# B45100557C.net
KiCad netlist of a schematic drawn in Altium Designer
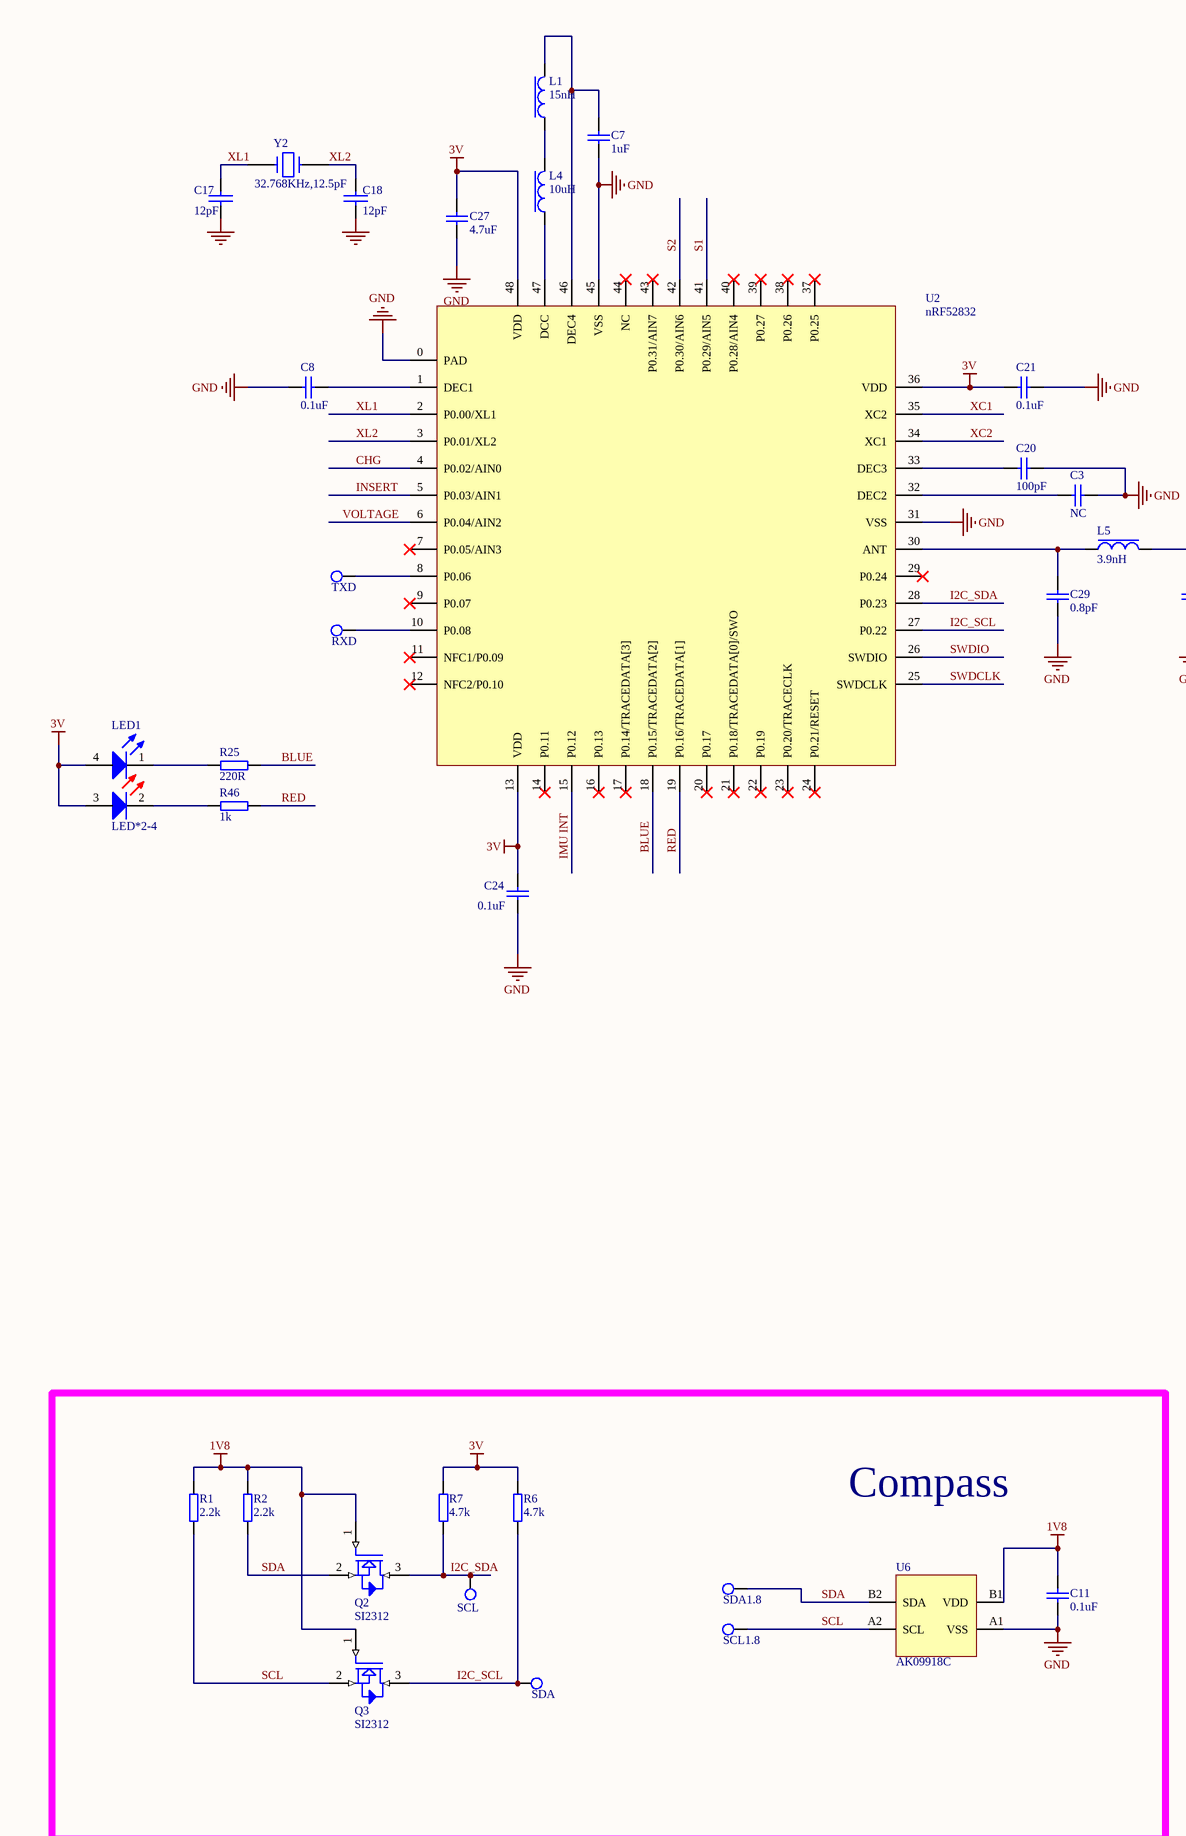
[diagram p0: B45100557C.SCHDOC, left]
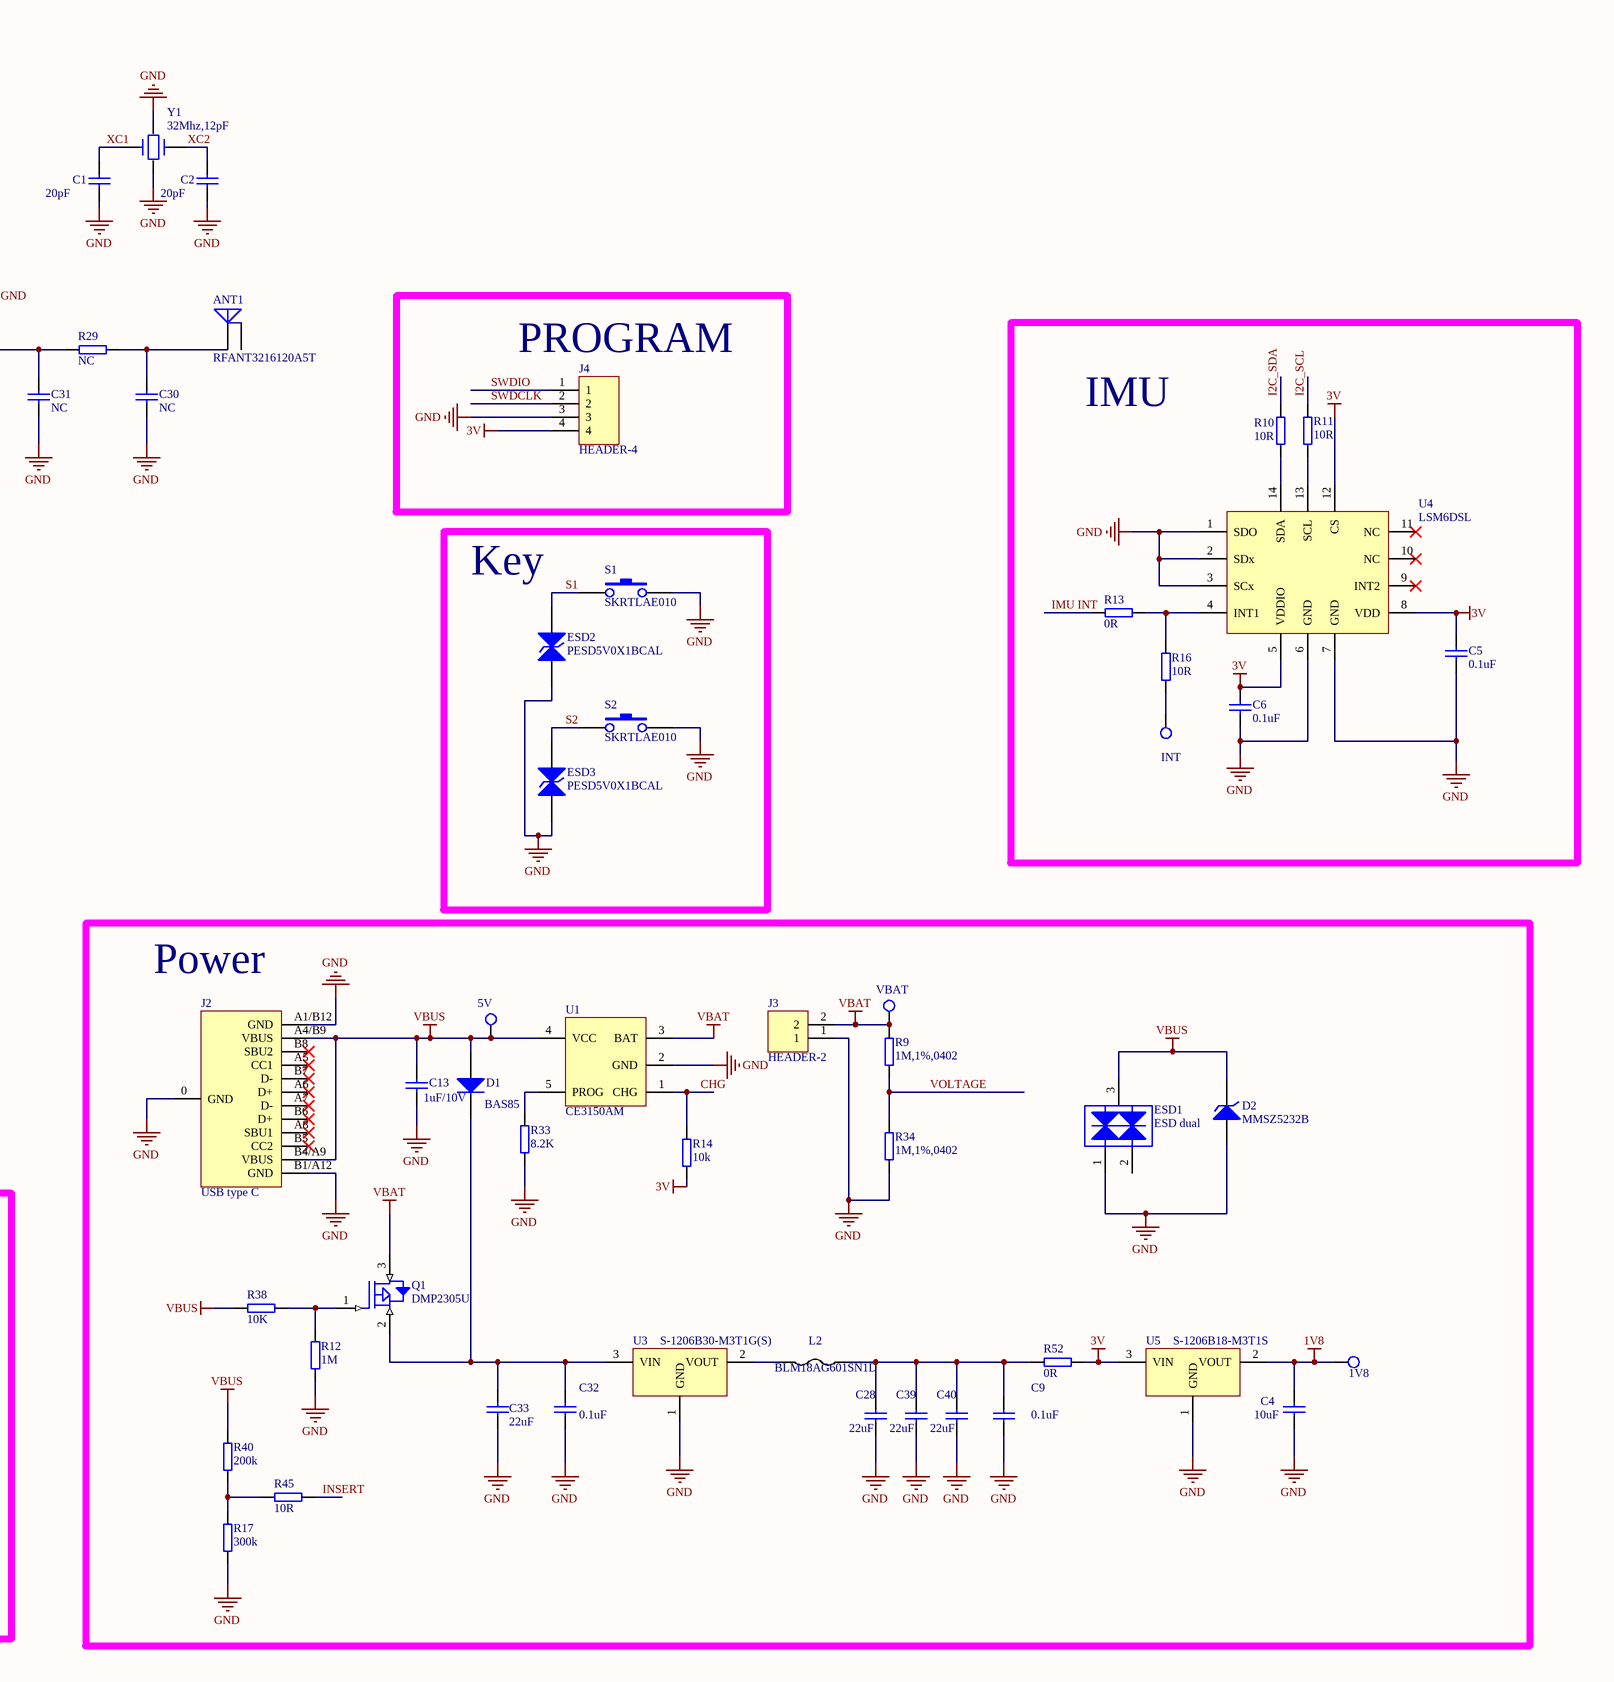
[diagram p1: B45100557C.SCHDOC, right]

(export (version "E")
  (design (tool "Eeschema 10.0.6"))
  (components
    (comp (ref "1V8") (value "TAP") (footprint "TS-1.0") (libsource (lib "dusun01-SCH") (part "TAP")))
    (comp (ref "5V") (value "TAP") (footprint "TS-1.0") (libsource (lib "dusun01-SCH") (part "TAP")))
    (comp (ref "ANT1")
      (value "RFANT3216120A5T")
      (footprint "RFANT3216120A1T")
      (libsource (lib "dusun01-SCH") (part "ANTENNA"))
    )
    (comp (ref "C1") (value "20pF") (footprint "C-0402") (libsource (lib "dusun01-SCH") (part "CAP")))
    (comp (ref "C2") (value "20pF") (footprint "C-0402") (libsource (lib "dusun01-SCH") (part "CAP")))
    (comp (ref "C3") (value "NC") (footprint "C-0402") (libsource (lib "dusun01-SCH") (part "CAP")))
    (comp (ref "C4") (value "10uF") (footprint "C-0603") (libsource (lib "dusun01-SCH") (part "CAP")))
    (comp (ref "C5")
      (value "0.1uF")
      (footprint "C-0402")
      (description "capacitor 27 pF NPO , +/- 2 %, SMD case 0603")
      (fields
        (field (name "MANUFACTURER") "Generic Components")
        (field (name "PUBLISHER") "Altium Hobart Technology Centre")
      )
      (libsource (lib "Miscellaneous Devices") (part "Cap"))
    )
    (comp (ref "C6")
      (value "0.1uF")
      (footprint "C-0402")
      (description "capacitor 27 pF NPO , +/- 2 %, SMD case 0603")
      (fields
        (field (name "MANUFACTURER") "Generic Components")
        (field (name "PUBLISHER") "Altium Hobart Technology Centre")
      )
      (libsource (lib "Miscellaneous Devices") (part "Cap"))
    )
    (comp (ref "C7") (value "1uF") (footprint "C-0402") (libsource (lib "dusun01-SCH") (part "CAP")))
    (comp (ref "C8") (value "0.1uF") (footprint "C-0402") (libsource (lib "dusun01-SCH") (part "CAP")))
    (comp (ref "C9") (value "0.1uF") (footprint "C-0402") (libsource (lib "dusun01-SCH") (part "CAP")))
    (comp (ref "C11")
      (value "0.1uF")
      (footprint "C-0402")
      (description "capacitor 27 pF NPO , +/- 2 %, SMD case 0603")
      (fields
        (field (name "MANUFACTURER") "Generic Components")
        (field (name "PUBLISHER") "Altium Hobart Technology Centre")
      )
      (libsource (lib "Miscellaneous Devices") (part "Cap"))
    )
    (comp (ref "C13") (value "1uF/10V") (footprint "C-0402") (libsource (lib "dusun01-SCH") (part "CAP")))
    (comp (ref "C17")
      (value "12pF")
      (footprint "dusun01-pcb:C-0402")
      (description "Capacitor")
      (libsource (lib "") (part "CAP_1"))
    )
    (comp (ref "C18")
      (value "12pF")
      (footprint "dusun01-pcb:C-0402")
      (description "Capacitor")
      (libsource (lib "") (part "CAP_1"))
    )
    (comp (ref "C20") (value "100pF") (footprint "C-0402") (libsource (lib "dusun01-SCH") (part "CAP")))
    (comp (ref "C21") (value "0.1uF") (footprint "C-0402") (libsource (lib "dusun01-SCH") (part "CAP")))
    (comp (ref "C24") (value "0.1uF") (footprint "C-0402") (libsource (lib "dusun01-SCH") (part "CAP")))
    (comp (ref "C27") (value "4.7uF") (footprint "C-0603") (libsource (lib "dusun01-SCH") (part "CAP")))
    (comp (ref "C28") (value "22uF") (footprint "C-0805") (libsource (lib "dusun01-SCH") (part "CAP")))
    (comp (ref "C29") (value "0.8pF") (footprint "C-0402") (libsource (lib "dusun01-SCH") (part "CAP")))
    (comp (ref "C30") (value "NC") (footprint "C-0402") (libsource (lib "dusun01-SCH") (part "CAP")))
    (comp (ref "C31") (value "NC") (footprint "C-0402") (libsource (lib "dusun01-SCH") (part "CAP")))
    (comp (ref "C32") (value "0.1uF") (footprint "C-0402") (libsource (lib "dusun01-SCH") (part "CAP")))
    (comp (ref "C33") (value "22uF") (footprint "dusun01-pcb:C-0805") (libsource (lib "*") (part "CAP")))
    (comp (ref "C39") (value "22uF") (footprint "C-0805") (libsource (lib "dusun01-SCH") (part "CAP")))
    (comp (ref "C40") (value "22uF") (footprint "C-0805") (libsource (lib "dusun01-SCH") (part "CAP")))
    (comp (ref "D1") (value "BAS85") (footprint "SOD-80") (libsource (lib "dusun01-SCH") (part "DIODE")))
    (comp (ref "D2") (value "MMSZ5232B") (footprint "sod-123") (libsource (lib "dusun01-SCH") (part "ZENER")))
    (comp (ref "ESD1")
      (value "ESD dual")
      (footprint "SOT-23")
      (libsource (lib "dusun01-SCH") (part "ESD dual"))
    )
    (comp (ref "ESD2")
      (value "PESD5V0X1BCAL")
      (footprint "R-0402")
      (libsource (lib "dusun01-SCH") (part "ESD"))
    )
    (comp (ref "ESD3")
      (value "PESD5V0X1BCAL")
      (footprint "R-0402")
      (libsource (lib "dusun01-SCH") (part "ESD"))
    )
    (comp (ref "INT") (value "TAP") (footprint "TS-1.0") (libsource (lib "dusun01-SCH") (part "TAP")))
    (comp (ref "J2")
      (value "USB type C")
      (footprint "USB type C")
      (libsource (lib "dusun01-SCH") (part "USB type C"))
    )
    (comp (ref "J3")
      (value "HEADER-2")
      (footprint "1.25T-2AWB")
      (libsource (lib "dusun01-SCH") (part "HEADER-2"))
    )
    (comp (ref "J4")
      (value "HEADER-4")
      (footprint "PH-4-2.54-1")
      (libsource (lib "dusun01-SCH") (part "HEADER-4"))
    )
    (comp (ref "L1") (value "15nH") (footprint "R-0402") (libsource (lib "dusun01-SCH") (part "INDUCTOR")))
    (comp (ref "L2")
      (value "BLM18AG601SN1D")
      (footprint "dusun01-pcb:R-0603")
      (libsource (lib "*") (part "Inductance"))
    )
    (comp (ref "L4")
      (value "10uH")
      (footprint "dusun02-pcb:R-0805")
      (libsource (lib "dusun01-SCH") (part "INDUCTOR"))
    )
    (comp (ref "L5") (value "3.9nH") (footprint "R-0402") (libsource (lib "dusun01-SCH") (part "INDUCTOR")))
    (comp (ref "LED1")
      (value "LED*2-4")
      (footprint "A-SP1942R6B1C-A01-2T")
      (libsource (lib "dusun01-SCH") (part "LED*2-4"))
    )
    (comp (ref "Q1")
      (value "DMP2305U")
      (footprint "SOT-23")
      (libsource (lib "dusun01-SCH") (part "MOSFET P"))
    )
    (comp (ref "Q2") (value "SI2312") (footprint "SOT-23") (libsource (lib "dusun01-SCH") (part "MOSFET N")))
    (comp (ref "Q3") (value "SI2312") (footprint "SOT-23") (libsource (lib "dusun01-SCH") (part "MOSFET N")))
    (comp (ref "R1") (value "2.2k") (footprint "R-0402") (libsource (lib "dusun01-SCH") (part "RES")))
    (comp (ref "R2") (value "2.2k") (footprint "R-0402") (libsource (lib "dusun01-SCH") (part "RES")))
    (comp (ref "R6") (value "4.7k") (footprint "R-0402") (libsource (lib "dusun01-SCH") (part "RES")))
    (comp (ref "R7") (value "4.7k") (footprint "R-0402") (libsource (lib "dusun01-SCH") (part "RES")))
    (comp (ref "R9") (value "1M,1%,0402") (footprint "R-0402") (libsource (lib "dusun01-SCH") (part "RES")))
    (comp (ref "R10") (value "10R") (footprint "R-0402") (libsource (lib "dusun01-SCH") (part "RES")))
    (comp (ref "R11") (value "10R") (footprint "R-0402") (libsource (lib "dusun01-SCH") (part "RES")))
    (comp (ref "R12") (value "1M") (footprint "R-0402") (libsource (lib "dusun01-SCH") (part "RES")))
    (comp (ref "R13") (value "0R") (footprint "R-0402") (libsource (lib "dusun01-SCH") (part "RES")))
    (comp (ref "R14") (value "10k") (footprint "R-0402") (libsource (lib "dusun01-SCH") (part "RES")))
    (comp (ref "R16") (value "10R") (footprint "R-0402") (libsource (lib "dusun01-SCH") (part "RES")))
    (comp (ref "R17") (value "300k") (footprint "R-0402") (libsource (lib "dusun01-SCH") (part "RES")))
    (comp (ref "R25") (value "220R") (footprint "R-0402") (libsource (lib "dusun01-SCH") (part "RES")))
    (comp (ref "R29") (value "NC") (footprint "R-0402") (libsource (lib "dusun01-SCH") (part "RES")))
    (comp (ref "R33") (value "8.2K") (footprint "R-0402") (libsource (lib "dusun01-SCH") (part "RES")))
    (comp (ref "R34") (value "1M,1%,0402") (footprint "R-0402") (libsource (lib "dusun01-SCH") (part "RES")))
    (comp (ref "R38") (value "10K") (footprint "R-0402") (libsource (lib "dusun01-SCH") (part "RES")))
    (comp (ref "R40") (value "200k") (footprint "R-0402") (libsource (lib "dusun01-SCH") (part "RES")))
    (comp (ref "R45") (value "10R") (footprint "R-0402") (libsource (lib "dusun01-SCH") (part "RES")))
    (comp (ref "R46") (value "1k") (footprint "R-0402") (libsource (lib "dusun01-SCH") (part "RES")))
    (comp (ref "R52") (value "0R") (footprint "R-0603") (libsource (lib "dusun01-SCH") (part "RES")))
    (comp (ref "RXD") (value "TAP") (footprint "TS-1.0") (libsource (lib "dusun01-SCH") (part "TAP")))
    (comp (ref "S1") (value "SKRTLAE010") (footprint "SKRTLAE010") (libsource (lib "dusun") (part "SW-PB")))
    (comp (ref "S2") (value "SKRTLAE010") (footprint "SKRTLAE010") (libsource (lib "dusun") (part "SW-PB")))
    (comp (ref "SCL") (value "TAP") (footprint "TS-1.0") (libsource (lib "dusun01-SCH") (part "TAP")))
    (comp (ref "SCL1.8") (value "TAP") (footprint "TS-1.0") (libsource (lib "dusun01-SCH") (part "TAP")))
    (comp (ref "SDA") (value "TAP") (footprint "TS-1.0") (libsource (lib "dusun01-SCH") (part "TAP")))
    (comp (ref "SDA1.8") (value "TAP") (footprint "TS-1.0") (libsource (lib "dusun01-SCH") (part "TAP")))
    (comp (ref "TXD") (value "TAP") (footprint "TS-1.0") (libsource (lib "dusun01-SCH") (part "TAP")))
    (comp (ref "U1")
      (value "CE3150AM")
      (footprint "SOT-23-5")
      (libsource (lib "dusun01-SCH") (part "CE3150AM"))
    )
    (comp (ref "U2")
      (value "nRF52832")
      (footprint "QFN-48-6*6-0.4")
      (libsource (lib "dusun01-SCH") (part "nRF52832"))
    )
    (comp (ref "U3")
      (value "S-1206B30-M3T1G(S)")
      (footprint "SOT-23")
      (libsource (lib "dusun01-SCH") (part "S-1206BXX"))
    )
    (comp (ref "U4") (value "LSM6DSL") (footprint "LGA14") (libsource (lib "dusun01-SCH") (part "LSM6DSL")))
    (comp (ref "U5")
      (value "S-1206B18-M3T1S")
      (footprint "SOT-23")
      (libsource (lib "dusun01-SCH") (part "S-1206BXX"))
    )
    (comp (ref "U6")
      (value "AK09918C")
      (footprint "AK09918C")
      (libsource (lib "dusun01-SCH") (part "AK09918C"))
    )
    (comp (ref "VBAT") (value "TAP") (footprint "TS-1.0") (libsource (lib "dusun01-SCH") (part "TAP")))
    (comp (ref "Y1")
      (value "32Mhz,12pF")
      (footprint "XD3225-1-12M-125M")
      (libsource (lib "dusun01-SCH") (part "CRYSTAL4"))
    )
    (comp (ref "Y2")
      (value "32.768KHz,12.5pF")
      (footprint "32.768Khz-3215")
      (libsource (lib "dusun01-SCH") (part "CRYSTAL2"))
    )
  )
  (nets
    (net (code "1") (name "/BLUE") (class "Default")
      (node (ref "R25") (pin "1") (pinfunction "1_1") (pintype "passive"))
      (node (ref "U2") (pin "18") (pinfunction "P0.15/TRACEDATA[2]_18") (pintype "passive"))
    )
    (net (code "2") (name "/CHG") (class "Default")
      (node (ref "R14") (pin "2") (pinfunction "2_2") (pintype "passive"))
      (node (ref "U1") (pin "1") (pinfunction "CHG_1") (pintype "passive"))
      (node (ref "U2") (pin "4") (pinfunction "P0.02/AIN0_4") (pintype "passive"))
    )
    (net (code "3") (name "/I2C_SCL") (class "Default")
      (node (ref "Q3") (pin "3") (pinfunction "D_3") (pintype "input"))
      (node (ref "R11") (pin "2") (pinfunction "2_2") (pintype "passive"))
      (node (ref "R6") (pin "2") (pinfunction "2_2") (pintype "passive"))
      (node (ref "SDA") (pin "1") (pinfunction "1_1") (pintype "passive"))
      (node (ref "U2") (pin "27") (pinfunction "P0.22_27") (pintype "passive"))
    )
    (net (code "4") (name "/I2C_SDA") (class "Default")
      (node (ref "Q2") (pin "3") (pinfunction "D_3") (pintype "input"))
      (node (ref "R10") (pin "2") (pinfunction "2_2") (pintype "passive"))
      (node (ref "R7") (pin "2") (pinfunction "2_2") (pintype "passive"))
      (node (ref "SCL") (pin "1") (pinfunction "1_1") (pintype "passive"))
      (node (ref "U2") (pin "28") (pinfunction "P0.23_28") (pintype "passive"))
    )
    (net (code "5") (name "/IMU INT") (class "Default")
      (node (ref "R13") (pin "1") (pinfunction "1_1") (pintype "passive"))
      (node (ref "U2") (pin "15") (pinfunction "P0.12_15") (pintype "passive"))
    )
    (net (code "6") (name "/INSERT") (class "Default")
      (node (ref "R45") (pin "1") (pinfunction "1_1") (pintype "passive"))
      (node (ref "U2") (pin "5") (pinfunction "P0.03/AIN1_5") (pintype "passive"))
    )
    (net (code "7") (name "/RED") (class "Default")
      (node (ref "R46") (pin "1") (pinfunction "1_1") (pintype "passive"))
      (node (ref "U2") (pin "19") (pinfunction "P0.16/TRACEDATA[1]_19") (pintype "passive"))
    )
    (net (code "8") (name "/S1") (class "Default")
      (node (ref "ESD2") (pin "2") (pinfunction "2_2") (pintype "passive"))
      (node (ref "S1") (pin "2") (pinfunction "2_2") (pintype "passive"))
      (node (ref "U2") (pin "41") (pinfunction "P0.29/AIN5_41") (pintype "passive"))
    )
    (net (code "9") (name "/S2") (class "Default")
      (node (ref "ESD3") (pin "2") (pinfunction "2_2") (pintype "passive"))
      (node (ref "S2") (pin "2") (pinfunction "2_2") (pintype "passive"))
      (node (ref "U2") (pin "42") (pinfunction "P0.30/AIN6_42") (pintype "passive"))
    )
    (net (code "10") (name "/SCL") (class "Default")
      (node (ref "Q3") (pin "2") (pinfunction "S_2") (pintype "input"))
      (node (ref "R1") (pin "2") (pinfunction "2_2") (pintype "passive"))
      (node (ref "SCL1.8") (pin "1") (pinfunction "1_1") (pintype "passive"))
      (node (ref "U6") (pin "A2") (pinfunction "SCL_A2") (pintype "passive"))
    )
    (net (code "11") (name "/SDA") (class "Default")
      (node (ref "Q2") (pin "2") (pinfunction "S_2") (pintype "input"))
      (node (ref "R2") (pin "2") (pinfunction "2_2") (pintype "passive"))
      (node (ref "SDA1.8") (pin "1") (pinfunction "1_1") (pintype "passive"))
      (node (ref "U6") (pin "B2") (pinfunction "SDA_B2") (pintype "passive"))
    )
    (net (code "12") (name "/SWDCLK") (class "Default")
      (node (ref "J4") (pin "2") (pinfunction "2_2") (pintype "passive"))
      (node (ref "U2") (pin "25") (pinfunction "SWDCLK_25") (pintype "passive"))
    )
    (net (code "13") (name "/SWDIO") (class "Default")
      (node (ref "J4") (pin "1") (pinfunction "1_1") (pintype "passive"))
      (node (ref "U2") (pin "26") (pinfunction "SWDIO_26") (pintype "passive"))
    )
    (net (code "14") (name "/VOLTAGE") (class "Default")
      (node (ref "R34") (pin "2") (pinfunction "2_2") (pintype "passive"))
      (node (ref "R9") (pin "1") (pinfunction "1_1") (pintype "passive"))
      (node (ref "U2") (pin "6") (pinfunction "P0.04/AIN2_6") (pintype "passive"))
    )
    (net (code "15") (name "/XC1") (class "Default")
      (node (ref "C1") (pin "1") (pinfunction "1_1") (pintype "passive"))
      (node (ref "U2") (pin "35") (pinfunction "XC2_35") (pintype "passive"))
      (node (ref "Y1") (pin "1") (pinfunction "1_1") (pintype "passive"))
    )
    (net (code "16") (name "/XC2") (class "Default")
      (node (ref "C2") (pin "1") (pinfunction "1_1") (pintype "passive"))
      (node (ref "U2") (pin "34") (pinfunction "XC1_34") (pintype "passive"))
      (node (ref "Y1") (pin "2") (pinfunction "2_2") (pintype "passive"))
    )
    (net (code "17") (name "/XL1") (class "Default")
      (node (ref "C17") (pin "1") (pinfunction "1_1") (pintype "passive"))
      (node (ref "U2") (pin "2") (pinfunction "P0.00/XL1_2") (pintype "passive"))
      (node (ref "Y2") (pin "1") (pinfunction "1_1") (pintype "passive"))
    )
    (net (code "18") (name "/XL2") (class "Default")
      (node (ref "C18") (pin "1") (pinfunction "1_1") (pintype "passive"))
      (node (ref "U2") (pin "3") (pinfunction "P0.01/XL2_3") (pintype "passive"))
      (node (ref "Y2") (pin "2") (pinfunction "2_2") (pintype "passive"))
    )
    (net (code "19") (name "1V8") (class "Default")
      (node (ref "1V8") (pin "1") (pinfunction "1_1") (pintype "passive"))
      (node (ref "C11") (pin "1") (pinfunction "1_1") (pintype "passive"))
      (node (ref "C4") (pin "1") (pinfunction "1_1") (pintype "passive"))
      (node (ref "Q2") (pin "1") (pinfunction "G_1") (pintype "input"))
      (node (ref "Q3") (pin "1") (pinfunction "G_1") (pintype "input"))
      (node (ref "R1") (pin "1") (pinfunction "1_1") (pintype "passive"))
      (node (ref "R2") (pin "1") (pinfunction "1_1") (pintype "passive"))
      (node (ref "U5") (pin "2") (pinfunction "VOUT_2") (pintype "passive"))
      (node (ref "U6") (pin "B1") (pinfunction "VDD_B1") (pintype "passive"))
    )
    (net (code "20") (name "3V") (class "Default")
      (node (ref "C21") (pin "1") (pinfunction "1_1") (pintype "passive"))
      (node (ref "C24") (pin "1") (pinfunction "1_1") (pintype "passive"))
      (node (ref "C27") (pin "1") (pinfunction "1_1") (pintype "passive"))
      (node (ref "C5") (pin "1") (pinfunction "1_1") (pintype "passive"))
      (node (ref "C6") (pin "1") (pinfunction "1_1") (pintype "passive"))
      (node (ref "J4") (pin "4") (pinfunction "4_4") (pintype "passive"))
      (node (ref "LED1") (pin "3") (pinfunction "3_3") (pintype "passive"))
      (node (ref "LED1") (pin "4") (pinfunction "4_4") (pintype "passive"))
      (node (ref "R14") (pin "1") (pinfunction "1_1") (pintype "passive"))
      (node (ref "R52") (pin "1") (pinfunction "1_1") (pintype "passive"))
      (node (ref "R6") (pin "1") (pinfunction "1_1") (pintype "passive"))
      (node (ref "R7") (pin "1") (pinfunction "1_1") (pintype "passive"))
      (node (ref "U2") (pin "13") (pinfunction "VDD_13") (pintype "passive"))
      (node (ref "U2") (pin "36") (pinfunction "VDD_36") (pintype "passive"))
      (node (ref "U2") (pin "48") (pinfunction "VDD_48") (pintype "passive"))
      (node (ref "U4") (pin "12") (pinfunction "CS_12") (pintype "passive"))
      (node (ref "U4") (pin "5") (pinfunction "VDDIO_5") (pintype "passive"))
      (node (ref "U4") (pin "8") (pinfunction "VDD_8") (pintype "passive"))
      (node (ref "U5") (pin "3") (pinfunction "VIN_3") (pintype "passive"))
    )
    (net (code "21") (name "GND") (class "Default")
      (node (ref "C1") (pin "2") (pinfunction "2_2") (pintype "passive"))
      (node (ref "C11") (pin "2") (pinfunction "2_2") (pintype "passive"))
      (node (ref "C13") (pin "2") (pinfunction "2_2") (pintype "passive"))
      (node (ref "C17") (pin "2") (pinfunction "2_2") (pintype "passive"))
      (node (ref "C18") (pin "2") (pinfunction "2_2") (pintype "passive"))
      (node (ref "C2") (pin "2") (pinfunction "2_2") (pintype "passive"))
      (node (ref "C20") (pin "2") (pinfunction "2_2") (pintype "passive"))
      (node (ref "C21") (pin "2") (pinfunction "2_2") (pintype "passive"))
      (node (ref "C24") (pin "2") (pinfunction "2_2") (pintype "passive"))
      (node (ref "C27") (pin "2") (pinfunction "2_2") (pintype "passive"))
      (node (ref "C28") (pin "2") (pinfunction "2_2") (pintype "passive"))
      (node (ref "C29") (pin "2") (pinfunction "2_2") (pintype "passive"))
      (node (ref "C3") (pin "2") (pinfunction "2_2") (pintype "passive"))
      (node (ref "C30") (pin "2") (pinfunction "2_2") (pintype "passive"))
      (node (ref "C31") (pin "2") (pinfunction "2_2") (pintype "passive"))
      (node (ref "C32") (pin "2") (pinfunction "2_2") (pintype "passive"))
      (node (ref "C33") (pin "2") (pinfunction "2_2") (pintype "passive"))
      (node (ref "C39") (pin "2") (pinfunction "2_2") (pintype "passive"))
      (node (ref "C4") (pin "2") (pinfunction "2_2") (pintype "passive"))
      (node (ref "C40") (pin "2") (pinfunction "2_2") (pintype "passive"))
      (node (ref "C5") (pin "2") (pinfunction "2_2") (pintype "passive"))
      (node (ref "C6") (pin "2") (pinfunction "2_2") (pintype "passive"))
      (node (ref "C7") (pin "1") (pinfunction "1_1") (pintype "passive"))
      (node (ref "C8") (pin "1") (pinfunction "1_1") (pintype "passive"))
      (node (ref "C9") (pin "2") (pinfunction "2_2") (pintype "passive"))
      (node (ref "D2") (pin "1") (pinfunction "1_1") (pintype "passive"))
      (node (ref "ESD1") (pin "1") (pinfunction "1_1") (pintype "passive"))
      (node (ref "ESD2") (pin "1") (pinfunction "1_1") (pintype "passive"))
      (node (ref "ESD3") (pin "1") (pinfunction "1_1") (pintype "passive"))
      (node (ref "J2") (pin "0") (pinfunction "GND_0") (pintype "passive"))
      (node (ref "J2") (pin "A1/B12") (pinfunction "GND_A1/B12") (pintype "passive"))
      (node (ref "J2") (pin "B1/A12") (pinfunction "GND_B1/A12") (pintype "passive"))
      (node (ref "J3") (pin "1") (pinfunction "1_1") (pintype "passive"))
      (node (ref "J4") (pin "3") (pinfunction "3_3") (pintype "passive"))
      (node (ref "R12") (pin "1") (pinfunction "1_1") (pintype "passive"))
      (node (ref "R17") (pin "1") (pinfunction "1_1") (pintype "passive"))
      (node (ref "R33") (pin "1") (pinfunction "1_1") (pintype "passive"))
      (node (ref "R34") (pin "1") (pinfunction "1_1") (pintype "passive"))
      (node (ref "S1") (pin "1") (pinfunction "1_1") (pintype "passive"))
      (node (ref "S2") (pin "1") (pinfunction "1_1") (pintype "passive"))
      (node (ref "U1") (pin "2") (pinfunction "GND_2") (pintype "passive"))
      (node (ref "U2") (pin "0") (pinfunction "PAD_0") (pintype "passive"))
      (node (ref "U2") (pin "31") (pinfunction "VSS_31") (pintype "passive"))
      (node (ref "U2") (pin "45") (pinfunction "VSS_45") (pintype "passive"))
      (node (ref "U3") (pin "1") (pinfunction "GND_1") (pintype "passive"))
      (node (ref "U4") (pin "1") (pinfunction "SDO_1") (pintype "passive"))
      (node (ref "U4") (pin "2") (pinfunction "SDx_2") (pintype "passive"))
      (node (ref "U4") (pin "3") (pinfunction "SCx_3") (pintype "passive"))
      (node (ref "U4") (pin "6") (pinfunction "GND_6") (pintype "passive"))
      (node (ref "U4") (pin "7") (pinfunction "GND_7") (pintype "passive"))
      (node (ref "U5") (pin "1") (pinfunction "GND_1") (pintype "passive"))
      (node (ref "U6") (pin "A1") (pinfunction "VSS_A1") (pintype "passive"))
      (node (ref "Y1") (pin "3") (pinfunction "3_3") (pintype "passive"))
    )
    (net (code "22") (name "Net-(ANT1-Pad1)") (class "Default")
      (node (ref "ANT1") (pin "1") (pinfunction "1_1") (pintype "passive"))
      (node (ref "C30") (pin "1") (pinfunction "1_1") (pintype "passive"))
      (node (ref "R29") (pin "2") (pinfunction "2_2") (pintype "passive"))
    )
    (net (code "23") (name "Net-(C28-Pad1)") (class "Default")
      (node (ref "C28") (pin "1") (pinfunction "1_1") (pintype "passive"))
      (node (ref "C39") (pin "1") (pinfunction "1_1") (pintype "passive"))
      (node (ref "C40") (pin "1") (pinfunction "1_1") (pintype "passive"))
      (node (ref "C9") (pin "1") (pinfunction "1_1") (pintype "passive"))
      (node (ref "L2") (pin "1") (pintype "passive"))
      (node (ref "R52") (pin "2") (pinfunction "2_2") (pintype "passive"))
    )
    (net (code "24") (name "Net-(C31-Pad1)") (class "Default")
      (node (ref "C31") (pin "1") (pinfunction "1_1") (pintype "passive"))
      (node (ref "L5") (pin "2") (pinfunction "2_2") (pintype "passive"))
      (node (ref "R29") (pin "1") (pinfunction "1_1") (pintype "passive"))
    )
    (net (code "25") (name "Net-(INT-Pad1)") (class "Default")
      (node (ref "INT") (pin "1") (pinfunction "1_1") (pintype "passive"))
      (node (ref "R16") (pin "1") (pinfunction "1_1") (pintype "passive"))
    )
    (net (code "26") (name "Net-(L1-Pad1)") (class "Default")
      (node (ref "L1") (pin "1") (pinfunction "1_1") (pintype "passive"))
      (node (ref "L4") (pin "2") (pinfunction "2_2") (pintype "passive"))
    )
    (net (code "27") (name "Net-(LED1-Pad1)") (class "Default")
      (node (ref "LED1") (pin "1") (pinfunction "1_1") (pintype "passive"))
      (node (ref "R25") (pin "2") (pinfunction "2_2") (pintype "passive"))
    )
    (net (code "28") (name "Net-(LED1-Pad2)") (class "Default")
      (node (ref "LED1") (pin "2") (pinfunction "2_2") (pintype "passive"))
      (node (ref "R46") (pin "2") (pinfunction "2_2") (pintype "passive"))
    )
    (net (code "29") (name "Net-(Q1-G)") (class "Default")
      (node (ref "Q1") (pin "1") (pinfunction "G_1") (pintype "input"))
      (node (ref "R12") (pin "2") (pinfunction "2_2") (pintype "passive"))
      (node (ref "R38") (pin "1") (pinfunction "1_1") (pintype "passive"))
    )
    (net (code "30") (name "Net-(Q1-S)") (class "Default")
      (node (ref "C32") (pin "1") (pinfunction "1_1") (pintype "passive"))
      (node (ref "C33") (pin "1") (pinfunction "1_1") (pintype "passive"))
      (node (ref "D1") (pin "2") (pinfunction "2_2") (pintype "passive"))
      (node (ref "Q1") (pin "2") (pinfunction "S_2") (pintype "input"))
      (node (ref "U3") (pin "3") (pinfunction "VIN_3") (pintype "passive"))
    )
    (net (code "31") (name "Net-(R17-Pad2)") (class "Default")
      (node (ref "R17") (pin "2") (pinfunction "2_2") (pintype "passive"))
      (node (ref "R40") (pin "1") (pinfunction "1_1") (pintype "passive"))
      (node (ref "R45") (pin "2") (pinfunction "2_2") (pintype "passive"))
    )
    (net (code "32") (name "Net-(U1-PROG)") (class "Default")
      (node (ref "R33") (pin "2") (pinfunction "2_2") (pintype "passive"))
      (node (ref "U1") (pin "5") (pinfunction "PROG_5") (pintype "passive"))
    )
    (net (code "33") (name "Net-(U2-ANT)") (class "Default")
      (node (ref "C29") (pin "1") (pinfunction "1_1") (pintype "passive"))
      (node (ref "L5") (pin "1") (pinfunction "1_1") (pintype "passive"))
      (node (ref "U2") (pin "30") (pinfunction "ANT_30") (pintype "passive"))
    )
    (net (code "34") (name "Net-(U2-DCC)") (class "Default")
      (node (ref "L4") (pin "1") (pinfunction "1_1") (pintype "passive"))
      (node (ref "U2") (pin "47") (pinfunction "DCC_47") (pintype "passive"))
    )
    (net (code "35") (name "Net-(U2-DEC1)") (class "Default")
      (node (ref "C8") (pin "2") (pinfunction "2_2") (pintype "passive"))
      (node (ref "U2") (pin "1") (pinfunction "DEC1_1") (pintype "passive"))
    )
    (net (code "36") (name "Net-(U2-DEC2)") (class "Default")
      (node (ref "C3") (pin "1") (pinfunction "1_1") (pintype "passive"))
      (node (ref "U2") (pin "32") (pinfunction "DEC2_32") (pintype "passive"))
    )
    (net (code "37") (name "Net-(U2-DEC3)") (class "Default")
      (node (ref "C20") (pin "1") (pinfunction "1_1") (pintype "passive"))
      (node (ref "U2") (pin "33") (pinfunction "DEC3_33") (pintype "passive"))
    )
    (net (code "38") (name "Net-(U2-DEC4)") (class "Default")
      (node (ref "C7") (pin "2") (pinfunction "2_2") (pintype "passive"))
      (node (ref "L1") (pin "2") (pinfunction "2_2") (pintype "passive"))
      (node (ref "U2") (pin "46") (pinfunction "DEC4_46") (pintype "passive"))
    )
    (net (code "39") (name "Net-(U2-P0.06)") (class "Default")
      (node (ref "TXD") (pin "1") (pinfunction "1_1") (pintype "passive"))
      (node (ref "U2") (pin "8") (pinfunction "P0.06_8") (pintype "passive"))
    )
    (net (code "40") (name "Net-(U2-P0.08)") (class "Default")
      (node (ref "RXD") (pin "1") (pinfunction "1_1") (pintype "passive"))
      (node (ref "U2") (pin "10") (pinfunction "P0.08_10") (pintype "passive"))
    )
    (net (code "41") (name "Net-(U3-VOUT)") (class "Default")
      (node (ref "L2") (pin "2") (pintype "passive"))
      (node (ref "U3") (pin "2") (pinfunction "VOUT_2") (pintype "passive"))
    )
    (net (code "42") (name "Net-(U4-INT1)") (class "Default")
      (node (ref "R13") (pin "2") (pinfunction "2_2") (pintype "passive"))
      (node (ref "R16") (pin "2") (pinfunction "2_2") (pintype "passive"))
      (node (ref "U4") (pin "4") (pinfunction "INT1_4") (pintype "passive"))
    )
    (net (code "43") (name "Net-(U4-SCL)") (class "Default")
      (node (ref "R11") (pin "1") (pinfunction "1_1") (pintype "passive"))
      (node (ref "U4") (pin "13") (pinfunction "SCL_13") (pintype "passive"))
    )
    (net (code "44") (name "Net-(U4-SDA)") (class "Default")
      (node (ref "R10") (pin "1") (pinfunction "1_1") (pintype "passive"))
      (node (ref "U4") (pin "14") (pinfunction "SDA_14") (pintype "passive"))
    )
    (net (code "45") (name "VBAT") (class "Default")
      (node (ref "J3") (pin "2") (pinfunction "2_2") (pintype "passive"))
      (node (ref "Q1") (pin "3") (pinfunction "D_3") (pintype "input"))
      (node (ref "R9") (pin "2") (pinfunction "2_2") (pintype "passive"))
      (node (ref "U1") (pin "3") (pinfunction "BAT_3") (pintype "passive"))
      (node (ref "VBAT") (pin "1") (pinfunction "1_1") (pintype "passive"))
    )
    (net (code "46") (name "VBUS") (class "Default")
      (node (ref "5V") (pin "1") (pinfunction "1_1") (pintype "passive"))
      (node (ref "C13") (pin "1") (pinfunction "1_1") (pintype "passive"))
      (node (ref "D1") (pin "1") (pinfunction "1_1") (pintype "passive"))
      (node (ref "D2") (pin "2") (pinfunction "2_2") (pintype "passive"))
      (node (ref "ESD1") (pin "3") (pinfunction "3_3") (pintype "passive"))
      (node (ref "J2") (pin "A4/B9") (pinfunction "VBUS_A4/B9") (pintype "passive"))
      (node (ref "J2") (pin "B4/A9") (pinfunction "VBUS_B4/A9") (pintype "passive"))
      (node (ref "R38") (pin "2") (pinfunction "2_2") (pintype "passive"))
      (node (ref "R40") (pin "2") (pinfunction "2_2") (pintype "passive"))
      (node (ref "U1") (pin "4") (pinfunction "VCC_4") (pintype "passive"))
    )
    (net (code "47") (name "unconnected-(ANT1-Pad2)") (class "Default")
      (node (ref "ANT1") (pin "2") (pinfunction "2_2") (pintype "passive"))
    )
    (net (code "48") (name "unconnected-(ESD1-Pad2)") (class "Default")
      (node (ref "ESD1") (pin "2") (pinfunction "2_2") (pintype "passive"))
    )
    (net (code "49") (name "unconnected-(J2-CC1-PadA5)") (class "Default")
      (node (ref "J2") (pin "A5") (pinfunction "CC1_A5") (pintype "passive+no_connect"))
    )
    (net (code "50") (name "unconnected-(J2-CC2-PadB5)") (class "Default")
      (node (ref "J2") (pin "B5") (pinfunction "CC2_B5") (pintype "passive+no_connect"))
    )
    (net (code "51") (name "unconnected-(J2-D+-PadA6)") (class "Default")
      (node (ref "J2") (pin "A6") (pinfunction "D+_A6") (pintype "passive+no_connect"))
    )
    (net (code "52") (name "unconnected-(J2-D+-PadB6)") (class "Default")
      (node (ref "J2") (pin "B6") (pinfunction "D+_B6") (pintype "passive+no_connect"))
    )
    (net (code "53") (name "unconnected-(J2-D--PadA7)") (class "Default")
      (node (ref "J2") (pin "A7") (pinfunction "D-_A7") (pintype "passive+no_connect"))
    )
    (net (code "54") (name "unconnected-(J2-D--PadB7)") (class "Default")
      (node (ref "J2") (pin "B7") (pinfunction "D-_B7") (pintype "passive+no_connect"))
    )
    (net (code "55") (name "unconnected-(J2-SBU1-PadA8)") (class "Default")
      (node (ref "J2") (pin "A8") (pinfunction "SBU1_A8") (pintype "passive+no_connect"))
    )
    (net (code "56") (name "unconnected-(J2-SBU2-PadB8)") (class "Default")
      (node (ref "J2") (pin "B8") (pinfunction "SBU2_B8") (pintype "passive+no_connect"))
    )
    (net (code "57") (name "unconnected-(U2-NC-Pad44)") (class "Default")
      (node (ref "U2") (pin "44") (pinfunction "NC_44") (pintype "passive+no_connect"))
    )
    (net (code "58") (name "unconnected-(U2-NFC1{slash}P0.09-Pad11)") (class "Default")
      (node (ref "U2") (pin "11") (pinfunction "NFC1/P0.09_11") (pintype "passive+no_connect"))
    )
    (net (code "59") (name "unconnected-(U2-NFC2{slash}P0.10-Pad12)") (class "Default")
      (node (ref "U2") (pin "12") (pinfunction "NFC2/P0.10_12") (pintype "passive+no_connect"))
    )
    (net (code "60") (name "unconnected-(U2-P0.05{slash}AIN3-Pad7)") (class "Default")
      (node (ref "U2") (pin "7") (pinfunction "P0.05/AIN3_7") (pintype "passive+no_connect"))
    )
    (net (code "61") (name "unconnected-(U2-P0.07-Pad9)") (class "Default")
      (node (ref "U2") (pin "9") (pinfunction "P0.07_9") (pintype "passive+no_connect"))
    )
    (net (code "62") (name "unconnected-(U2-P0.11-Pad14)") (class "Default")
      (node (ref "U2") (pin "14") (pinfunction "P0.11_14") (pintype "passive+no_connect"))
    )
    (net (code "63") (name "unconnected-(U2-P0.13-Pad16)") (class "Default")
      (node (ref "U2") (pin "16") (pinfunction "P0.13_16") (pintype "passive+no_connect"))
    )
    (net (code "64") (name "unconnected-(U2-P0.14{slash}TRACEDATA[3]-Pad17)") (class "Default")
      (node (ref "U2") (pin "17") (pinfunction "P0.14/TRACEDATA[3]_17") (pintype "passive+no_connect"))
    )
    (net (code "65") (name "unconnected-(U2-P0.17-Pad20)") (class "Default")
      (node (ref "U2") (pin "20") (pinfunction "P0.17_20") (pintype "passive+no_connect"))
    )
    (net (code "66") (name "unconnected-(U2-P0.18{slash}TRACEDATA[0]{slash}SWO-Pad21)") (class "Default")
      (node (ref "U2") (pin "21") (pinfunction "P0.18/TRACEDATA[0]/SWO_21") (pintype "passive+no_connect"))
    )
    (net (code "67") (name "unconnected-(U2-P0.19-Pad22)") (class "Default")
      (node (ref "U2") (pin "22") (pinfunction "P0.19_22") (pintype "passive+no_connect"))
    )
    (net (code "68") (name "unconnected-(U2-P0.20{slash}TRACECLK-Pad23)") (class "Default")
      (node (ref "U2") (pin "23") (pinfunction "P0.20/TRACECLK_23") (pintype "passive+no_connect"))
    )
    (net (code "69") (name "unconnected-(U2-P0.21{slash}RESET-Pad24)") (class "Default")
      (node (ref "U2") (pin "24") (pinfunction "P0.21/RESET_24") (pintype "passive+no_connect"))
    )
    (net (code "70") (name "unconnected-(U2-P0.24-Pad29)") (class "Default")
      (node (ref "U2") (pin "29") (pinfunction "P0.24_29") (pintype "passive+no_connect"))
    )
    (net (code "71") (name "unconnected-(U2-P0.25-Pad37)") (class "Default")
      (node (ref "U2") (pin "37") (pinfunction "P0.25_37") (pintype "passive+no_connect"))
    )
    (net (code "72") (name "unconnected-(U2-P0.26-Pad38)") (class "Default")
      (node (ref "U2") (pin "38") (pinfunction "P0.26_38") (pintype "passive+no_connect"))
    )
    (net (code "73") (name "unconnected-(U2-P0.27-Pad39)") (class "Default")
      (node (ref "U2") (pin "39") (pinfunction "P0.27_39") (pintype "passive+no_connect"))
    )
    (net (code "74") (name "unconnected-(U2-P0.28{slash}AIN4-Pad40)") (class "Default")
      (node (ref "U2") (pin "40") (pinfunction "P0.28/AIN4_40") (pintype "passive+no_connect"))
    )
    (net (code "75") (name "unconnected-(U2-P0.31{slash}AIN7-Pad43)") (class "Default")
      (node (ref "U2") (pin "43") (pinfunction "P0.31/AIN7_43") (pintype "passive+no_connect"))
    )
    (net (code "76") (name "unconnected-(U4-INT2-Pad9)") (class "Default")
      (node (ref "U4") (pin "9") (pinfunction "INT2_9") (pintype "passive+no_connect"))
    )
    (net (code "77") (name "unconnected-(U4-NC-Pad10)") (class "Default")
      (node (ref "U4") (pin "10") (pinfunction "NC_10") (pintype "passive+no_connect"))
    )
    (net (code "78") (name "unconnected-(U4-NC-Pad11)") (class "Default")
      (node (ref "U4") (pin "11") (pinfunction "NC_11") (pintype "passive+no_connect"))
    )
  )
)
